# Sheet1.net
KiCad netlist of a schematic drawn in Altium Designer
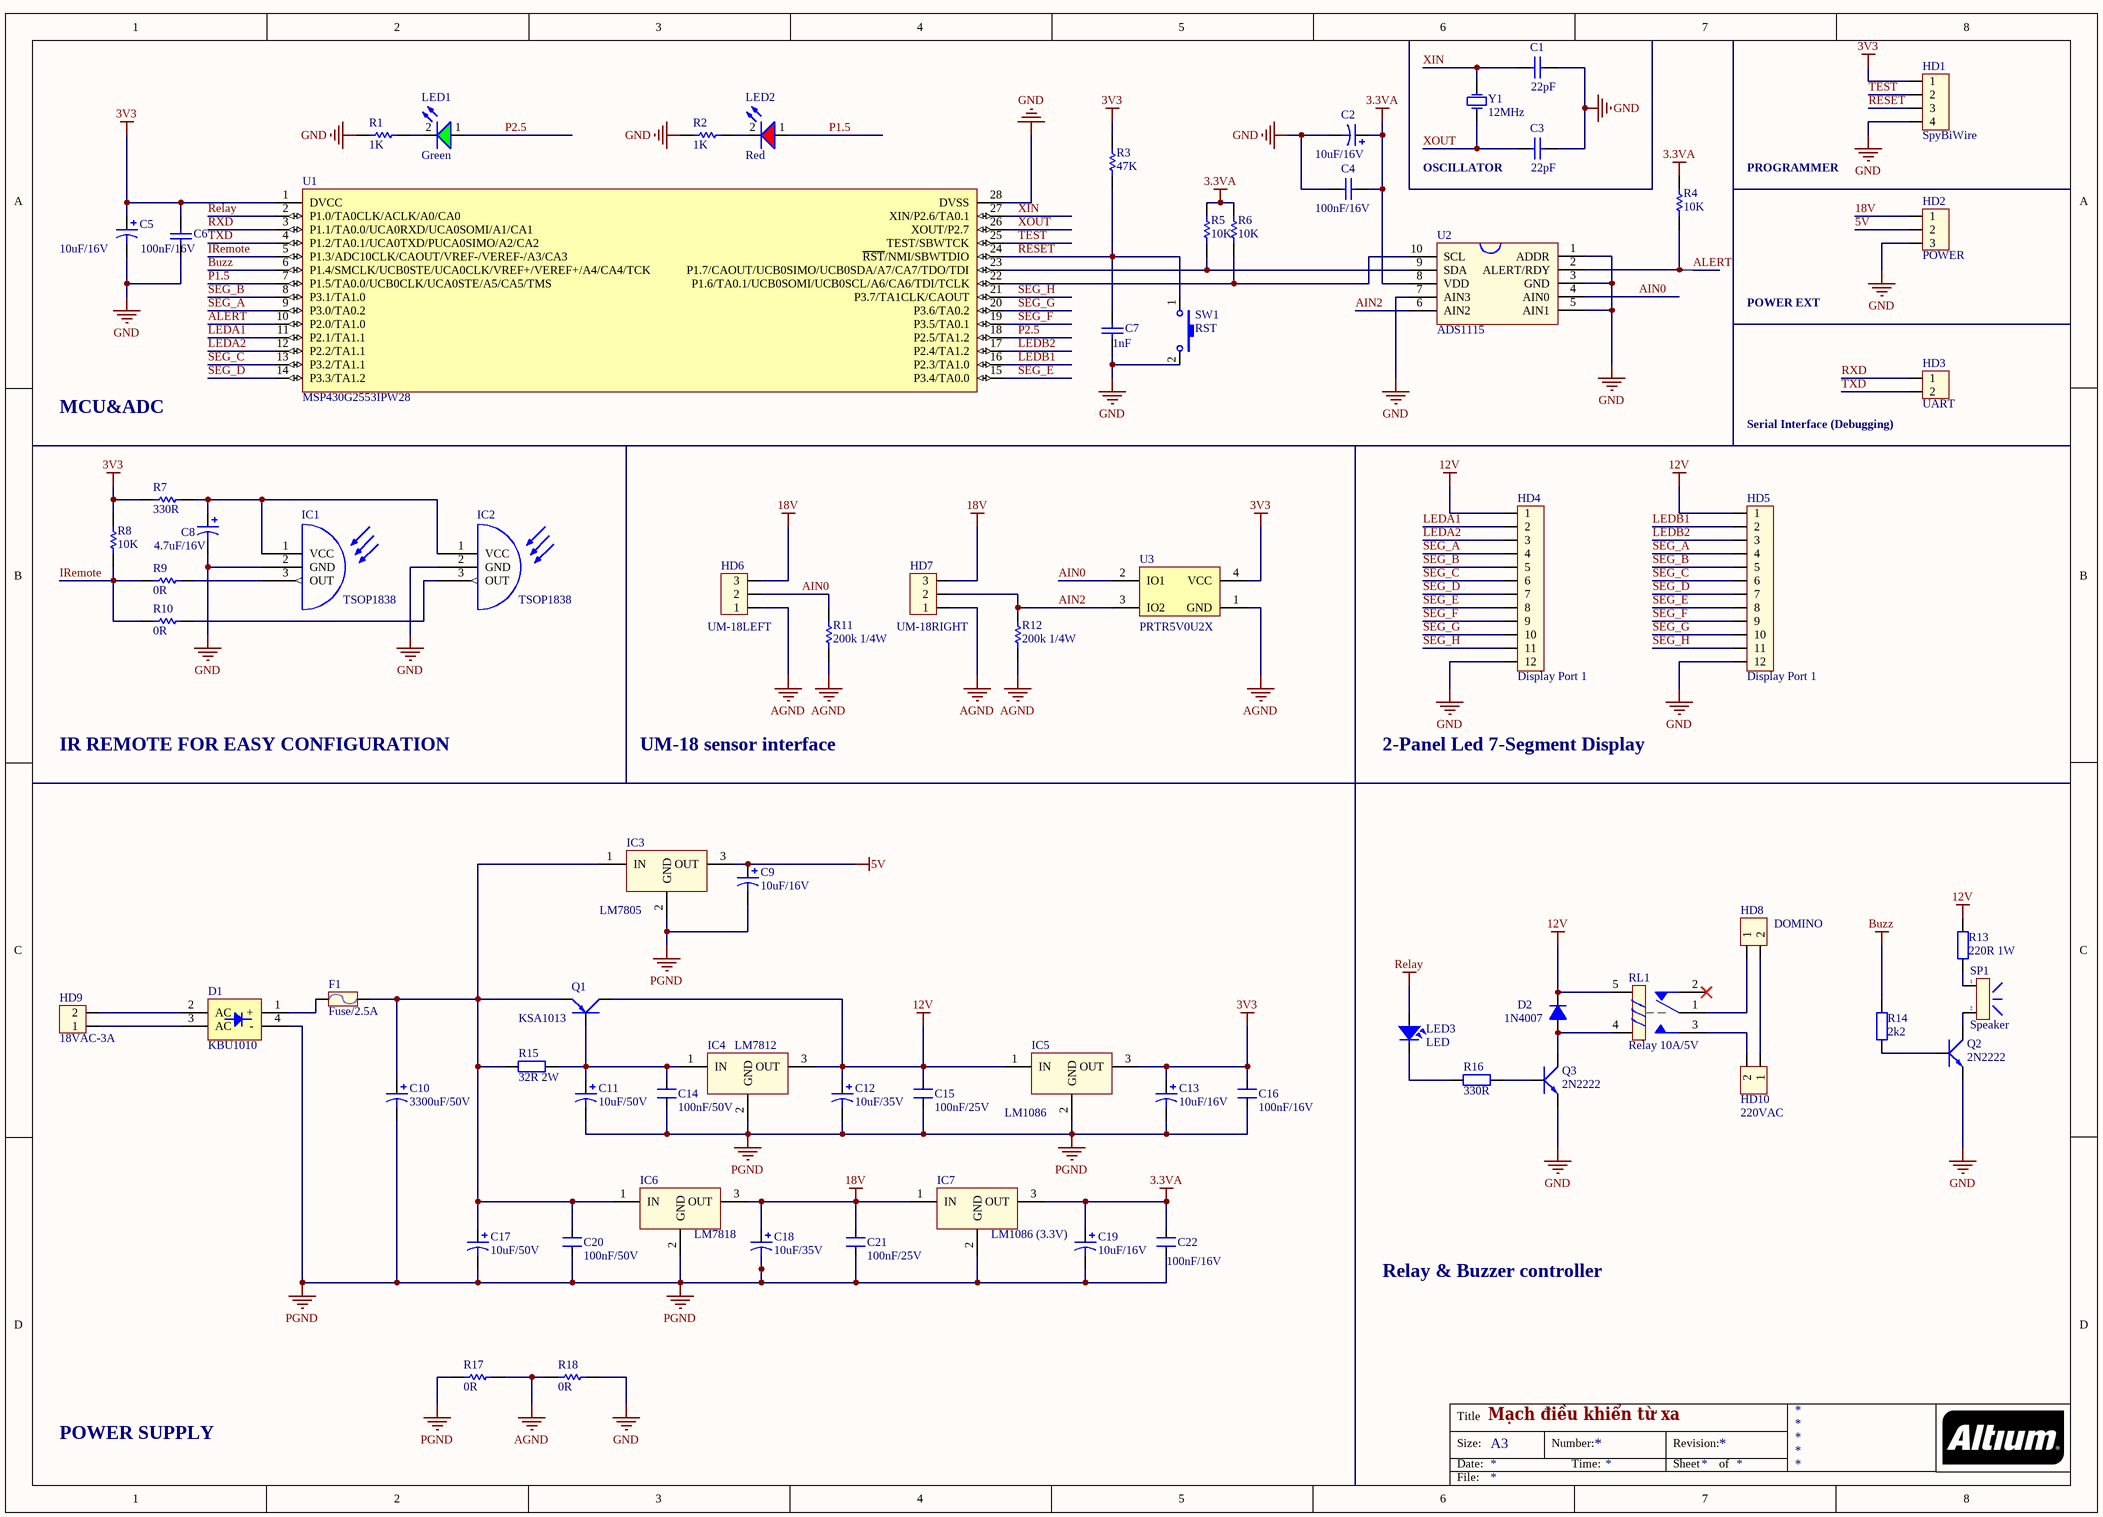
[diagram p0: Sheet1.SchDoc]

(export (version "E")
  (design (tool "Eeschema 10.0.6"))
  (components
    (comp (ref "C1")
      (value "22pF")
      (footprint "Tu gom 104")
      (description "CAP CER 10000PF 50V X7R 0603")
      (fields
        (field (name "MANUFACTURER") "Murata Electronics North America")
        (field (name "MANUFACTURER PART NUMBER") "GRM188R71H103KA01D")
      )
      (libsource (lib "lpson") (part "10nF/50V/C0603/10%"))
    )
    (comp (ref "C2")
      (value "10uF/16V")
      (footprint "CAP_22UF_16V")
      (description "CAP TANT 100UF 6.3V 20% 1411")
      (fields
        (field (name "MANUFACTURER") "Kemet")
        (field (name "MANUFACTURER PART NUMBER") "T491B107M006AT")
      )
      (libsource (lib "lpson") (part "100uF/6.3V/SIZE B/20%"))
    )
    (comp (ref "C3")
      (value "22pF")
      (footprint "Tu gom 104")
      (description "CAP CER 10000PF 50V X7R 0603")
      (fields
        (field (name "MANUFACTURER") "Murata Electronics North America")
        (field (name "MANUFACTURER PART NUMBER") "GRM188R71H103KA01D")
      )
      (libsource (lib "lpson") (part "10nF/50V/C0603/10%"))
    )
    (comp (ref "C4")
      (value "100nF/16V")
      (footprint "C0_1uF")
      (description "CAP CER 10000PF 50V X7R 0603")
      (fields
        (field (name "MANUFACTURER") "Murata Electronics North America")
        (field (name "MANUFACTURER PART NUMBER") "GRM188R71H103KA01D")
      )
      (libsource (lib "lpson") (part "10nF/50V/C0603/10%"))
    )
    (comp (ref "C5")
      (value "10uF/16V")
      (footprint "CP_1")
      (description "CAP TANT 100UF 6.3V 20% 1411")
      (fields
        (field (name "MANUFACTURER") "Kemet")
        (field (name "MANUFACTURER PART NUMBER") "T491B107M006AT")
      )
      (libsource (lib "lpson") (part "100uF/6.3V/SIZE B/20%"))
    )
    (comp (ref "C6")
      (value "100nF/16V")
      (footprint "Tu gom 104")
      (description "CAP CER 10000PF 50V X7R 0603")
      (fields
        (field (name "MANUFACTURER") "Murata Electronics North America")
        (field (name "MANUFACTURER PART NUMBER") "GRM188R71H103KA01D")
      )
      (libsource (lib "lpson") (part "10nF/50V/C0603/10%"))
    )
    (comp (ref "C7")
      (value "1nF")
      (footprint "Tu gom 104")
      (description "CAP CER 10000PF 50V X7R 0603")
      (fields
        (field (name "MANUFACTURER") "Murata Electronics North America")
        (field (name "MANUFACTURER PART NUMBER") "GRM188R71H103KA01D")
      )
      (libsource (lib "lpson") (part "10nF/50V/C0603/10%"))
    )
    (comp (ref "C8")
      (value "4.7uF/16V")
      (footprint "CP_1")
      (description "CAP TANT 100UF 6.3V 20% 1411")
      (fields
        (field (name "MANUFACTURER") "Kemet")
        (field (name "MANUFACTURER PART NUMBER") "T491B107M006AT")
      )
      (libsource (lib "lpson") (part "100uF/6.3V/SIZE B/20%"))
    )
    (comp (ref "C9")
      (value "10uF/16V")
      (footprint "CP_1")
      (description "Polarized Capacitor (Radial)")
      (fields (field (name "Comment") "Cap Pol1") (field (name "PUBLISHER") "Altium Limited"))
      (libsource (lib "lib_thien_schematic") (part "Cap Pol1"))
    )
    (comp (ref "C10")
      (value "3300uF/50V")
      (footprint "CAP_470UF_25V")
      (description "Polarized Capacitor (Radial)")
      (fields (field (name "Comment") "Cap Pol1") (field (name "PUBLISHER") "Altium Limited"))
      (libsource (lib "lib_thien_schematic") (part "Cap Pol1"))
    )
    (comp (ref "C11")
      (value "10uF/50V")
      (footprint "CP_1")
      (description "Polarized Capacitor (Radial)")
      (fields (field (name "Comment") "Cap Pol1") (field (name "PUBLISHER") "Altium Limited"))
      (libsource (lib "lib_thien_schematic") (part "Cap Pol1"))
    )
    (comp (ref "C12")
      (value "10uF/35V")
      (footprint "CP_1")
      (description "Polarized Capacitor (Radial)")
      (fields (field (name "Comment") "Cap Pol1") (field (name "PUBLISHER") "Altium Limited"))
      (libsource (lib "lib_thien_schematic") (part "Cap Pol1"))
    )
    (comp (ref "C13")
      (value "10uF/16V")
      (footprint "CP_1")
      (description "Polarized Capacitor (Radial)")
      (fields (field (name "Comment") "Cap Pol1") (field (name "PUBLISHER") "Altium Limited"))
      (libsource (lib "lib_thien_schematic") (part "Cap Pol1"))
    )
    (comp (ref "C14")
      (value "100nF/50V")
      (footprint "Tu gom 104")
      (description "Cap np 104 => 105pF")
      (libsource (lib "lib_thien_schematic") (part "CN2"))
    )
    (comp (ref "C15")
      (value "100nF/25V")
      (footprint "Tu gom 104")
      (description "Cap np 104 => 105pF")
      (libsource (lib "lib_thien_schematic") (part "CN2"))
    )
    (comp (ref "C16")
      (value "100nF/16V")
      (footprint "Tu gom 104")
      (description "Cap np 104 => 105pF")
      (libsource (lib "lib_thien_schematic") (part "CN2"))
    )
    (comp (ref "C17")
      (value "10uF/50V")
      (footprint "CP_1")
      (description "Polarized Capacitor (Radial)")
      (fields (field (name "Comment") "Cap Pol1") (field (name "PUBLISHER") "Altium Limited"))
      (libsource (lib "lib_thien_schematic") (part "Cap Pol1"))
    )
    (comp (ref "C18")
      (value "10uF/35V")
      (footprint "CP_1")
      (description "Polarized Capacitor (Radial)")
      (fields (field (name "Comment") "Cap Pol1") (field (name "PUBLISHER") "Altium Limited"))
      (libsource (lib "lib_thien_schematic") (part "Cap Pol1"))
    )
    (comp (ref "C19")
      (value "10uF/16V")
      (footprint "CP_1")
      (description "Polarized Capacitor (Radial)")
      (fields (field (name "Comment") "Cap Pol1") (field (name "PUBLISHER") "Altium Limited"))
      (libsource (lib "lib_thien_schematic") (part "Cap Pol1"))
    )
    (comp (ref "C20")
      (value "100nF/50V")
      (footprint "Tu gom 104")
      (description "Cap np 104 => 105pF")
      (libsource (lib "lib_thien_schematic") (part "CN2"))
    )
    (comp (ref "C21")
      (value "100nF/25V")
      (footprint "Tu gom 104")
      (description "Cap np 104 => 105pF")
      (libsource (lib "lib_thien_schematic") (part "CN2"))
    )
    (comp (ref "C22")
      (value "100nF/16V")
      (footprint "Tu gom 104")
      (description "Cap np 104 => 105pF")
      (libsource (lib "VNELEK") (part "CN2"))
    )
    (comp (ref "D1")
      (value "KBU1010")
      (footprint "BRIDGE-10A")
      (description "10A glass passivated bridge rectifier")
      (libsource (lib "lib_thien_schematic") (part "KBU1010"))
    )
    (comp (ref "D2")
      (value "1N4007")
      (footprint "D2A")
      (description "Diode 1A")
      (libsource (lib "VNELEK") (part "D1A"))
    )
    (comp (ref "F1")
      (value "Fuse/2.5A")
      (footprint "FUSE2_5A")
      (description "Fuse")
      (fields (field (name "DESIGNED BY") "VanDungEvn"))
      (libsource (lib "lib_thien_schematic") (part "Fuse"))
    )
    (comp (ref "HD1")
      (value "SpyBiWire")
      (footprint "Header_4")
      (description "Header 4 (Green)")
      (libsource (lib "lpson") (part "Hed4"))
    )
    (comp (ref "HD2")
      (value "POWER")
      (footprint "HD-3")
      (description "Header 3 (Green)")
      (libsource (lib "") (part "Hed3_1"))
    )
    (comp (ref "HD3")
      (value "UART")
      (footprint "HD2")
      (description "Header 2 (Green)")
      (libsource (lib "lpson") (part "Hed2"))
    )
    (comp (ref "HD4")
      (value "Display Port 1")
      (footprint "HD-12")
      (description "Header 12")
      (libsource (lib "lib_thien_schematic") (part "Hed12"))
    )
    (comp (ref "HD5")
      (value "Display Port 1")
      (footprint "HD-12")
      (description "Header 12")
      (libsource (lib "lib_thien_schematic") (part "Hed12"))
    )
    (comp (ref "HD6")
      (value "UM-18LEFT")
      (footprint "Header_3")
      (description "Header 3 (Green)")
      (libsource (lib "lpson") (part "Hed3"))
    )
    (comp (ref "HD7")
      (value "UM-18RIGHT")
      (footprint "Header_3")
      (description "Header 3 (Green)")
      (libsource (lib "lpson") (part "Hed3"))
    )
    (comp (ref "HD8")
      (value "DOMINO")
      (footprint "HDR-2GREEN")
      (description "Header 2 (Green)")
      (libsource (lib "lib_thien_schematic") (part "Hed2"))
    )
    (comp (ref "HD9")
      (value "18VAC-3A")
      (footprint "HDR-2GREEN")
      (description "Header 2 (Green)")
      (libsource (lib "") (part "Hed2_2"))
    )
    (comp (ref "HD10")
      (value "220VAC")
      (footprint "HDR-2GREEN")
      (description "Header 2 (Green)")
      (libsource (lib "") (part "Hed2_1"))
    )
    (comp (ref "IC1")
      (value "TSOP1838")
      (footprint "TSOP-1838")
      (libsource (lib "lib_thien_schematic") (part "TSOP1838"))
    )
    (comp (ref "IC2")
      (value "TSOP1838")
      (footprint "TSOP-1838")
      (libsource (lib "lib_thien_schematic") (part "TSOP1838"))
    )
    (comp (ref "IC3")
      (value "LM7805")
      (footprint "TO-220")
      (description "Linear Regulator")
      (libsource (lib "lib_thien_schematic") (part "LM78xx"))
    )
    (comp (ref "IC4")
      (value "LM7812")
      (footprint "TO-220")
      (description "Linear Regulator")
      (libsource (lib "lib_thien_schematic") (part "LM78xx"))
    )
    (comp (ref "IC5")
      (value "LM1086")
      (footprint "TO-220")
      (description "Linear Regulator")
      (libsource (lib "lib_thien_schematic") (part "LM78xx"))
    )
    (comp (ref "IC6")
      (value "LM7818")
      (footprint "TO-220")
      (description "Linear Regulator")
      (libsource (lib "VNELEK") (part "LM78xx"))
    )
    (comp (ref "IC7")
      (value "LM1086 (3.3V)")
      (footprint "TO-220")
      (description "Linear Regulator")
      (libsource (lib "VNELEK") (part "LM78xx"))
    )
    (comp (ref "LED1")
      (value "Green")
      (footprint "LED_0805_GREEN")
      (description "LED Green 3mm")
      (fields (field (name "Comment") "LED_G_3"))
      (libsource (lib "lpson") (part "LED_GREEN_3MM"))
    )
    (comp (ref "LED2")
      (value "Red")
      (footprint "LED_0805_RED")
      (description "LED Red 5mm")
      (fields (field (name "Comment") "LED_R_5"))
      (libsource (lib "lpson") (part "LED_RED_5MM"))
    )
    (comp (ref "LED3")
      (value "LED")
      (footprint "LED_BLUE_5mm")
      (description "LED Single colour Green and Red")
      (libsource (lib "VNELEK") (part "LED"))
    )
    (comp (ref "Q1")
      (value "KSA1013")
      (footprint "TO92")
      (description "PNP 600mW, ECB")
      (fields (field (name "MANUFACTURER") "Fairchild Semiconductor"))
      (libsource (lib "lib_thien_schematic") (part "A1015"))
    )
    (comp (ref "Q2")
      (value "2N2222")
      (footprint "TO92")
      (description "TRANS GP SS NPN LP 40V TO92")
      (libsource (lib "VNELEK") (part "C1815"))
    )
    (comp (ref "Q3")
      (value "2N2222")
      (footprint "TO92")
      (description "TRANS GP SS NPN LP 40V TO92")
      (libsource (lib "VNELEK") (part "C1815"))
    )
    (comp (ref "R1")
      (value "1K")
      (footprint "R1/2W")
      (description "RES SMD 10K OHM 1% 1/10W 0603")
      (fields
        (field (name "MANUFACTURER") "Yageo")
        (field (name "MANUFACTURER PART NUMBER") "RC0603FR-0710KL")
      )
      (libsource (lib "lpson") (part "10K/R0603/1%"))
    )
    (comp (ref "R2")
      (value "1K")
      (footprint "R1/2W")
      (description "RES SMD 10K OHM 1% 1/10W 0603")
      (fields
        (field (name "MANUFACTURER") "Yageo")
        (field (name "MANUFACTURER PART NUMBER") "RC0603FR-0710KL")
      )
      (libsource (lib "lpson") (part "10K/R0603/1%"))
    )
    (comp (ref "R3")
      (value "47K")
      (footprint "R1/4W")
      (description "RES SMD 10K OHM 1% 1/10W 0603")
      (fields
        (field (name "MANUFACTURER") "Yageo")
        (field (name "MANUFACTURER PART NUMBER") "RC0603FR-0710KL")
      )
      (libsource (lib "lpson") (part "10K/R0603/1%"))
    )
    (comp (ref "R4")
      (value "10K")
      (footprint "R1/2W")
      (description "RES SMD 10K OHM 1% 1/10W 0603")
      (fields
        (field (name "MANUFACTURER") "Yageo")
        (field (name "MANUFACTURER PART NUMBER") "RC0603FR-0710KL")
      )
      (libsource (lib "lpson") (part "10K/R0603/1%"))
    )
    (comp (ref "R5")
      (value "10K")
      (footprint "R1/2W")
      (description "RES SMD 10K OHM 1% 1/10W 0603")
      (fields
        (field (name "MANUFACTURER") "Yageo")
        (field (name "MANUFACTURER PART NUMBER") "RC0603FR-0710KL")
      )
      (libsource (lib "lpson") (part "10K/R0603/1%"))
    )
    (comp (ref "R6")
      (value "10K")
      (footprint "R1/2W")
      (description "RES SMD 10K OHM 1% 1/10W 0603")
      (fields
        (field (name "MANUFACTURER") "Yageo")
        (field (name "MANUFACTURER PART NUMBER") "RC0603FR-0710KL")
      )
      (libsource (lib "lpson") (part "10K/R0603/1%"))
    )
    (comp (ref "R7")
      (value "330R")
      (footprint "R_0805")
      (description "RES SMD 10K OHM 1% 1/10W 0603")
      (fields
        (field (name "MANUFACTURER") "Yageo")
        (field (name "MANUFACTURER PART NUMBER") "RC0603FR-0710KL")
      )
      (libsource (lib "lpson") (part "10K/R0603/1%"))
    )
    (comp (ref "R8")
      (value "10K")
      (footprint "R1/2W")
      (description "RES SMD 10K OHM 1% 1/10W 0603")
      (fields
        (field (name "MANUFACTURER") "Yageo")
        (field (name "MANUFACTURER PART NUMBER") "RC0603FR-0710KL")
      )
      (libsource (lib "lpson") (part "10K/R0603/1%"))
    )
    (comp (ref "R9")
      (value "0R")
      (footprint "R1W")
      (description "RES SMD 10K OHM 1% 1/10W 0603")
      (fields
        (field (name "MANUFACTURER") "Yageo")
        (field (name "MANUFACTURER PART NUMBER") "RC0603FR-0710KL")
      )
      (libsource (lib "lpson") (part "10K/R0603/1%"))
    )
    (comp (ref "R10")
      (value "0R")
      (footprint "R1W")
      (description "RES SMD 10K OHM 1% 1/10W 0603")
      (fields
        (field (name "MANUFACTURER") "Yageo")
        (field (name "MANUFACTURER PART NUMBER") "RC0603FR-0710KL")
      )
      (libsource (lib "lpson") (part "10K/R0603/1%"))
    )
    (comp (ref "R11")
      (value "200k 1/4W")
      (footprint "R1/4W")
      (description "RES SMD 10K OHM 1% 1/10W 0603")
      (fields
        (field (name "MANUFACTURER") "Yageo")
        (field (name "MANUFACTURER PART NUMBER") "RC0603FR-0710KL")
      )
      (libsource (lib "lpson") (part "10K/R0603/1%"))
    )
    (comp (ref "R12")
      (value "200k 1/4W")
      (footprint "R1/4W")
      (description "RES SMD 10K OHM 1% 1/10W 0603")
      (fields
        (field (name "MANUFACTURER") "Yageo")
        (field (name "MANUFACTURER PART NUMBER") "RC0603FR-0710KL")
      )
      (libsource (lib "lpson") (part "10K/R0603/1%"))
    )
    (comp (ref "R13")
      (value "220R 1W")
      (footprint "R_0805")
      (description "Resistor")
      (fields (field (name "Comment") "Res2") (field (name "PUBLISHER") "Altium Limited"))
      (libsource (lib "") (part "Res2_1"))
    )
    (comp (ref "R14")
      (value "2k2")
      (footprint "R1/2W")
      (description "Resistor")
      (fields (field (name "Comment") "Res2") (field (name "PUBLISHER") "Altium Limited"))
      (libsource (lib "") (part "Res2_1"))
    )
    (comp (ref "R15")
      (value "32R 2W")
      (footprint "R_0805")
      (description "Resistor")
      (fields (field (name "Comment") "Res2") (field (name "PUBLISHER") "Altium Limited"))
      (libsource (lib "lib_thien_schematic") (part "Res2"))
    )
    (comp (ref "R16")
      (value "330R")
      (footprint "R_0805")
      (description "Resistor")
      (fields (field (name "Comment") "Res2") (field (name "PUBLISHER") "Altium Limited"))
      (libsource (lib "Miscellaneous Devices") (part "Res2"))
    )
    (comp (ref "R17")
      (value "0R")
      (footprint "R1W")
      (description "RES SMD 10K OHM 1% 1/10W 0603")
      (fields
        (field (name "MANUFACTURER") "Yageo")
        (field (name "MANUFACTURER PART NUMBER") "RC0603FR-0710KL")
      )
      (libsource (lib "lpson") (part "10K/R0603/1%"))
    )
    (comp (ref "R18")
      (value "0R")
      (footprint "R1W")
      (description "RES SMD 10K OHM 1% 1/10W 0603")
      (fields
        (field (name "MANUFACTURER") "Yageo")
        (field (name "MANUFACTURER PART NUMBER") "RC0603FR-0710KL")
      )
      (libsource (lib "lpson") (part "10K/R0603/1%"))
    )
    (comp (ref "RL1")
      (value "Relay 10A/5V")
      (footprint "RL_SPDT_10A")
      (description "Relay SPDT,10A - 12VDC 5 Pin")
      (libsource (lib "VNELEK") (part "Relay 1"))
    )
    (comp (ref "SP1")
      (value "Speaker")
      (footprint "SPEAKER")
      (description "Speaker Chip")
      (libsource (lib "lib_thien_schematic") (part "SPK"))
    )
    (comp (ref "SW1")
      (value "RST")
      (footprint "SW-SMD")
      (description "Switch smd, 2PIN 6x4mm")
      (fields (field (name "Comment") "EVQ-PNF04M") (field (name "PUBLISHER") "Altium Limited"))
      (libsource (lib "lpson") (part "SW EVQ-PNF04M"))
    )
    (comp (ref "U1")
      (value "MSP430G2553IPW28")
      (footprint "TSSOP-28")
      (description "MCU 16bit 16KB 1.8-3.6V 16MHz TSSOP28")
      (libsource (lib "lpson") (part "MSP430G2553IPW28"))
    )
    (comp (ref "U2")
      (value "ADS1115")
      (footprint "TSSOP-10")
      (libsource (lib "lib_thien_schematic") (part "ADS1115"))
    )
    (comp (ref "U3")
      (value "PRTR5V0U2X")
      (footprint "SOT-143")
      (description "ESD protection diode")
      (libsource (lib "lib_thien_schematic") (part "PRTR5V0U2X"))
    )
    (comp (ref "Y1")
      (value "12MHz")
      (footprint "XTAL-12MHz")
      (description "Crystal Oscillator 30ppm 20.000MHz")
      (fields (field (name "Comment") "HC49S-20-C-30-30-F-20.000MHz"))
      (libsource (lib "lpson") (part "HC49S-20-C-30-30-F-20.000MHz"))
    )
  )
  (nets
    (net (code "1") (name "/AIN0") (class "Default")
      (node (ref "HD6") (pin "2") (pinfunction "2_2") (pintype "passive"))
      (node (ref "R11") (pin "2") (pinfunction "2_2") (pintype "passive"))
      (node (ref "U2") (pin "4") (pinfunction "AIN0_4") (pintype "passive"))
      (node (ref "U3") (pin "2") (pinfunction "IO1_2") (pintype "passive"))
    )
    (net (code "2") (name "/AIN2") (class "Default")
      (node (ref "HD7") (pin "2") (pinfunction "2_2") (pintype "passive"))
      (node (ref "R12") (pin "2") (pinfunction "2_2") (pintype "passive"))
      (node (ref "U2") (pin "6") (pinfunction "AIN2_6") (pintype "passive"))
      (node (ref "U3") (pin "3") (pinfunction "IO2_3") (pintype "passive"))
    )
    (net (code "3") (name "/ALERT") (class "Default")
      (node (ref "R4") (pin "1") (pinfunction "1_1") (pintype "passive"))
      (node (ref "U1") (pin "10") (pinfunction "P2.0/TA1.0_10") (pintype "bidirectional"))
      (node (ref "U2") (pin "2") (pinfunction "ALERT/RDY_2") (pintype "passive"))
    )
    (net (code "4") (name "/IRemote") (class "Default")
      (node (ref "R10") (pin "1") (pinfunction "1_1") (pintype "passive"))
      (node (ref "R8") (pin "1") (pinfunction "1_1") (pintype "passive"))
      (node (ref "R9") (pin "1") (pinfunction "1_1") (pintype "passive"))
      (node (ref "U1") (pin "5") (pinfunction "P1.3/ADC10CLK/CAOUT/VREF-/VEREF-/A3/CA3_5") (pintype "bidirectional"))
    )
    (net (code "5") (name "/LEDA1") (class "Default")
      (node (ref "HD4") (pin "2") (pinfunction "2_2") (pintype "passive"))
      (node (ref "U1") (pin "11") (pinfunction "P2.1/TA1.1_11") (pintype "bidirectional"))
    )
    (net (code "6") (name "/LEDA2") (class "Default")
      (node (ref "HD4") (pin "3") (pinfunction "3_3") (pintype "passive"))
      (node (ref "U1") (pin "12") (pinfunction "P2.2/TA1.1_12") (pintype "bidirectional"))
    )
    (net (code "7") (name "/LEDB1") (class "Default")
      (node (ref "HD5") (pin "2") (pinfunction "2_2") (pintype "passive"))
      (node (ref "U1") (pin "16") (pinfunction "P2.3/TA1.0_16") (pintype "bidirectional"))
    )
    (net (code "8") (name "/LEDB2") (class "Default")
      (node (ref "HD5") (pin "3") (pinfunction "3_3") (pintype "passive"))
      (node (ref "U1") (pin "17") (pinfunction "P2.4/TA1.2_17") (pintype "bidirectional"))
    )
    (net (code "9") (name "/P1.5") (class "Default")
      (node (ref "LED2") (pin "1") (pinfunction "A_1") (pintype "passive"))
      (node (ref "U1") (pin "7") (pinfunction "P1.5/TA0.0/UCB0CLK/UCA0STE/A5/CA5/TMS_7") (pintype "bidirectional"))
    )
    (net (code "10") (name "/P2.5") (class "Default")
      (node (ref "LED1") (pin "1") (pinfunction "A_1") (pintype "passive"))
      (node (ref "U1") (pin "18") (pinfunction "P2.5/TA1.2_18") (pintype "bidirectional"))
    )
    (net (code "11") (name "/RESET") (class "Default")
      (node (ref "C7") (pin "2") (pinfunction "2_2") (pintype "passive"))
      (node (ref "HD1") (pin "3") (pinfunction "3_3") (pintype "passive"))
      (node (ref "R3") (pin "1") (pinfunction "1_1") (pintype "passive"))
      (node (ref "SW1") (pin "1") (pinfunction "1_1") (pintype "passive"))
      (node (ref "U1") (pin "24") (pinfunction "~{RST}/NMI/SBWTDIO_24") (pintype "bidirectional"))
    )
    (net (code "12") (name "/RXD") (class "Default")
      (node (ref "HD3") (pin "1") (pinfunction "1_1") (pintype "passive"))
      (node (ref "U1") (pin "3") (pinfunction "P1.1/TA0.0/UCA0RXD/UCA0SOMI/A1/CA1_3") (pintype "bidirectional"))
    )
    (net (code "13") (name "/SEG_A") (class "Default")
      (node (ref "HD4") (pin "4") (pinfunction "4_4") (pintype "passive"))
      (node (ref "HD5") (pin "4") (pinfunction "4_4") (pintype "passive"))
      (node (ref "U1") (pin "9") (pinfunction "P3.0/TA0.2_9") (pintype "bidirectional"))
    )
    (net (code "14") (name "/SEG_B") (class "Default")
      (node (ref "HD4") (pin "5") (pinfunction "5_5") (pintype "passive"))
      (node (ref "HD5") (pin "5") (pinfunction "5_5") (pintype "passive"))
      (node (ref "U1") (pin "8") (pinfunction "P3.1/TA1.0_8") (pintype "bidirectional"))
    )
    (net (code "15") (name "/SEG_C") (class "Default")
      (node (ref "HD4") (pin "6") (pinfunction "6_6") (pintype "passive"))
      (node (ref "HD5") (pin "6") (pinfunction "6_6") (pintype "passive"))
      (node (ref "U1") (pin "13") (pinfunction "P3.2/TA1.1_13") (pintype "bidirectional"))
    )
    (net (code "16") (name "/SEG_D") (class "Default")
      (node (ref "HD4") (pin "7") (pinfunction "7_7") (pintype "passive"))
      (node (ref "HD5") (pin "7") (pinfunction "7_7") (pintype "passive"))
      (node (ref "U1") (pin "14") (pinfunction "P3.3/TA1.2_14") (pintype "bidirectional"))
    )
    (net (code "17") (name "/SEG_E") (class "Default")
      (node (ref "HD4") (pin "8") (pinfunction "8_8") (pintype "passive"))
      (node (ref "HD5") (pin "8") (pinfunction "8_8") (pintype "passive"))
      (node (ref "U1") (pin "15") (pinfunction "P3.4/TA0.0_15") (pintype "bidirectional"))
    )
    (net (code "18") (name "/SEG_F") (class "Default")
      (node (ref "HD4") (pin "9") (pinfunction "9_9") (pintype "passive"))
      (node (ref "HD5") (pin "9") (pinfunction "9_9") (pintype "passive"))
      (node (ref "U1") (pin "19") (pinfunction "P3.5/TA0.1_19") (pintype "bidirectional"))
    )
    (net (code "19") (name "/SEG_G") (class "Default")
      (node (ref "HD4") (pin "10") (pinfunction "10_10") (pintype "passive"))
      (node (ref "HD5") (pin "10") (pinfunction "10_10") (pintype "passive"))
      (node (ref "U1") (pin "20") (pinfunction "P3.6/TA0.2_20") (pintype "bidirectional"))
    )
    (net (code "20") (name "/SEG_H") (class "Default")
      (node (ref "HD4") (pin "11") (pinfunction "11_11") (pintype "passive"))
      (node (ref "HD5") (pin "11") (pinfunction "11_11") (pintype "passive"))
      (node (ref "U1") (pin "21") (pinfunction "P3.7/TA1CLK/CAOUT_21") (pintype "bidirectional"))
    )
    (net (code "21") (name "/TEST") (class "Default")
      (node (ref "HD1") (pin "2") (pinfunction "2_2") (pintype "passive"))
      (node (ref "U1") (pin "25") (pinfunction "TEST/SBWTCK_25") (pintype "bidirectional"))
    )
    (net (code "22") (name "/TXD") (class "Default")
      (node (ref "HD3") (pin "2") (pinfunction "2_2") (pintype "passive"))
      (node (ref "U1") (pin "4") (pinfunction "P1.2/TA0.1/UCA0TXD/PUCA0SIMO/A2/CA2_4") (pintype "bidirectional"))
    )
    (net (code "23") (name "/XIN") (class "Default")
      (node (ref "C1") (pin "1") (pinfunction "1_1") (pintype "passive"))
      (node (ref "U1") (pin "27") (pinfunction "XIN/P2.6/TA0.1_27") (pintype "bidirectional"))
      (node (ref "Y1") (pin "2") (pinfunction "OSC2_2") (pintype "passive"))
    )
    (net (code "24") (name "/XOUT") (class "Default")
      (node (ref "C3") (pin "1") (pinfunction "1_1") (pintype "passive"))
      (node (ref "U1") (pin "26") (pinfunction "XOUT/P2.7_26") (pintype "bidirectional"))
      (node (ref "Y1") (pin "1") (pinfunction "OSC1_1") (pintype "passive"))
    )
    (net (code "25") (name "3.3VA") (class "Default")
      (node (ref "C19") (pin "1") (pinfunction "1_1") (pintype "passive"))
      (node (ref "C2") (pin "1") (pinfunction "1_1") (pintype "passive"))
      (node (ref "C22") (pin "2") (pinfunction "2_2") (pintype "passive"))
      (node (ref "C4") (pin "2") (pinfunction "2_2") (pintype "passive"))
      (node (ref "IC7") (pin "3") (pinfunction "OUT_3") (pintype "passive"))
      (node (ref "R4") (pin "2") (pinfunction "2_2") (pintype "passive"))
      (node (ref "R5") (pin "2") (pinfunction "2_2") (pintype "passive"))
      (node (ref "R6") (pin "2") (pinfunction "2_2") (pintype "passive"))
      (node (ref "U2") (pin "8") (pinfunction "VDD_8") (pintype "passive"))
    )
    (net (code "26") (name "3V3") (class "Default")
      (node (ref "C13") (pin "1") (pinfunction "1_1") (pintype "passive"))
      (node (ref "C16") (pin "2") (pinfunction "2_2") (pintype "passive"))
      (node (ref "C5") (pin "1") (pinfunction "1_1") (pintype "passive"))
      (node (ref "C6") (pin "2") (pinfunction "2_2") (pintype "passive"))
      (node (ref "HD1") (pin "1") (pinfunction "1_1") (pintype "passive"))
      (node (ref "IC5") (pin "3") (pinfunction "OUT_3") (pintype "passive"))
      (node (ref "R3") (pin "2") (pinfunction "2_2") (pintype "passive"))
      (node (ref "R7") (pin "1") (pinfunction "1_1") (pintype "passive"))
      (node (ref "R8") (pin "2") (pinfunction "2_2") (pintype "passive"))
      (node (ref "U1") (pin "1") (pinfunction "DVCC_1") (pintype "power_in"))
      (node (ref "U3") (pin "4") (pinfunction "VCC_4") (pintype "passive"))
    )
    (net (code "27") (name "5V") (class "Default")
      (node (ref "C9") (pin "1") (pinfunction "1_1") (pintype "passive"))
      (node (ref "HD2") (pin "2") (pinfunction "2_2") (pintype "passive"))
      (node (ref "IC3") (pin "3") (pinfunction "OUT_3") (pintype "passive"))
    )
    (net (code "28") (name "12V") (class "Default")
      (node (ref "C12") (pin "1") (pinfunction "1_1") (pintype "passive"))
      (node (ref "C15") (pin "2") (pinfunction "2_2") (pintype "passive"))
      (node (ref "D2") (pin "2") (pinfunction "K_2") (pintype "passive"))
      (node (ref "HD4") (pin "1") (pinfunction "1_1") (pintype "passive"))
      (node (ref "HD5") (pin "1") (pinfunction "1_1") (pintype "passive"))
      (node (ref "IC4") (pin "3") (pinfunction "OUT_3") (pintype "passive"))
      (node (ref "IC5") (pin "1") (pinfunction "IN_1") (pintype "passive"))
      (node (ref "Q1") (pin "2") (pinfunction "C_2") (pintype "passive"))
      (node (ref "R13") (pin "2") (pinfunction "2_2") (pintype "passive"))
      (node (ref "RL1") (pin "5") (pinfunction "5_5") (pintype "passive"))
    )
    (net (code "29") (name "18V") (class "Default")
      (node (ref "C18") (pin "1") (pinfunction "1_1") (pintype "passive"))
      (node (ref "C21") (pin "2") (pinfunction "2_2") (pintype "passive"))
      (node (ref "HD2") (pin "1") (pinfunction "1_1") (pintype "passive"))
      (node (ref "HD6") (pin "3") (pinfunction "3_3") (pintype "passive"))
      (node (ref "HD7") (pin "3") (pinfunction "3_3") (pintype "passive"))
      (node (ref "IC6") (pin "3") (pinfunction "OUT_3") (pintype "passive"))
      (node (ref "IC7") (pin "1") (pinfunction "IN_1") (pintype "passive"))
    )
    (net (code "30") (name "AGND") (class "Default")
      (node (ref "HD6") (pin "1") (pinfunction "1_1") (pintype "passive"))
      (node (ref "HD7") (pin "1") (pinfunction "1_1") (pintype "passive"))
      (node (ref "R11") (pin "1") (pinfunction "1_1") (pintype "passive"))
      (node (ref "R12") (pin "1") (pinfunction "1_1") (pintype "passive"))
      (node (ref "R17") (pin "2") (pinfunction "2_2") (pintype "passive"))
      (node (ref "R18") (pin "1") (pinfunction "1_1") (pintype "passive"))
      (node (ref "U3") (pin "1") (pinfunction "GND_1") (pintype "passive"))
    )
    (net (code "31") (name "Buzz") (class "Default")
      (node (ref "R14") (pin "1") (pinfunction "1_1") (pintype "passive"))
      (node (ref "U1") (pin "6") (pinfunction "P1.4/SMCLK/UCB0STE/UCA0CLK/VREF+/VEREF+/A4/CA4/TCK_6") (pintype "bidirectional"))
    )
    (net (code "32") (name "GND") (class "Default")
      (node (ref "C1") (pin "2") (pinfunction "2_2") (pintype "passive"))
      (node (ref "C2") (pin "2") (pinfunction "2_2") (pintype "passive"))
      (node (ref "C3") (pin "2") (pinfunction "2_2") (pintype "passive"))
      (node (ref "C4") (pin "1") (pinfunction "1_1") (pintype "passive"))
      (node (ref "C5") (pin "2") (pinfunction "2_2") (pintype "passive"))
      (node (ref "C6") (pin "1") (pinfunction "1_1") (pintype "passive"))
      (node (ref "C7") (pin "1") (pinfunction "1_1") (pintype "passive"))
      (node (ref "C8") (pin "2") (pinfunction "2_2") (pintype "passive"))
      (node (ref "HD1") (pin "4") (pinfunction "4_4") (pintype "passive"))
      (node (ref "HD2") (pin "3") (pinfunction "3_3") (pintype "passive"))
      (node (ref "HD4") (pin "12") (pinfunction "12_12") (pintype "passive"))
      (node (ref "HD5") (pin "12") (pinfunction "12_12") (pintype "passive"))
      (node (ref "IC1") (pin "2") (pinfunction "GND_2") (pintype "power_in"))
      (node (ref "IC2") (pin "2") (pinfunction "GND_2") (pintype "power_in"))
      (node (ref "Q2") (pin "1") (pinfunction "E_1") (pintype "passive"))
      (node (ref "Q3") (pin "1") (pinfunction "E_1") (pintype "passive"))
      (node (ref "R1") (pin "2") (pinfunction "2_2") (pintype "passive"))
      (node (ref "R18") (pin "2") (pinfunction "2_2") (pintype "passive"))
      (node (ref "R2") (pin "2") (pinfunction "2_2") (pintype "passive"))
      (node (ref "SW1") (pin "2") (pinfunction "2_2") (pintype "passive"))
      (node (ref "U1") (pin "28") (pinfunction "DVSS_28") (pintype "power_in"))
      (node (ref "U2") (pin "1") (pinfunction "ADDR_1") (pintype "passive"))
      (node (ref "U2") (pin "3") (pinfunction "GND_3") (pintype "passive"))
      (node (ref "U2") (pin "5") (pinfunction "AIN1_5") (pintype "passive"))
      (node (ref "U2") (pin "7") (pinfunction "AIN3_7") (pintype "passive"))
    )
    (net (code "33") (name "Net-(D1-+)") (class "Default")
      (node (ref "D1") (pin "1") (pinfunction "+_1") (pintype "power_in"))
      (node (ref "F1") (pin "1") (pinfunction "1_1") (pintype "passive"))
    )
    (net (code "34") (name "Net-(D1-AC-Pad2)") (class "Default")
      (node (ref "D1") (pin "2") (pinfunction "AC_2") (pintype "power_in"))
      (node (ref "HD9") (pin "2") (pinfunction "2_2") (pintype "passive"))
    )
    (net (code "35") (name "Net-(D1-AC-Pad3)") (class "Default")
      (node (ref "D1") (pin "3") (pinfunction "AC_3") (pintype "power_in"))
      (node (ref "HD9") (pin "1") (pinfunction "1_1") (pintype "passive"))
    )
    (net (code "36") (name "Net-(D2-A)") (class "Default")
      (node (ref "D2") (pin "1") (pinfunction "A_1") (pintype "passive"))
      (node (ref "Q3") (pin "3") (pinfunction "C_3") (pintype "passive"))
      (node (ref "RL1") (pin "4") (pinfunction "4_4") (pintype "passive"))
    )
    (net (code "37") (name "Net-(HD8-Pad1)") (class "Default")
      (node (ref "HD8") (pin "1") (pinfunction "1_1") (pintype "passive"))
      (node (ref "RL1") (pin "1") (pinfunction "1_1") (pintype "passive"))
    )
    (net (code "38") (name "Net-(HD10-Pad1)") (class "Default")
      (node (ref "HD10") (pin "1") (pinfunction "1_1") (pintype "passive"))
      (node (ref "HD8") (pin "2") (pinfunction "2_2") (pintype "passive"))
    )
    (net (code "39") (name "Net-(HD10-Pad2)") (class "Default")
      (node (ref "HD10") (pin "2") (pinfunction "2_2") (pintype "passive"))
      (node (ref "RL1") (pin "3") (pinfunction "3_3") (pintype "passive"))
    )
    (net (code "40") (name "Net-(IC1-OUT)") (class "Default")
      (node (ref "IC1") (pin "3") (pinfunction "OUT_3") (pintype "output"))
      (node (ref "R9") (pin "2") (pinfunction "2_2") (pintype "passive"))
    )
    (net (code "41") (name "Net-(IC1-VCC)") (class "Default")
      (node (ref "C8") (pin "1") (pinfunction "1_1") (pintype "passive"))
      (node (ref "IC1") (pin "1") (pinfunction "VCC_1") (pintype "power_in"))
      (node (ref "IC2") (pin "1") (pinfunction "VCC_1") (pintype "power_in"))
      (node (ref "R7") (pin "2") (pinfunction "2_2") (pintype "passive"))
    )
    (net (code "42") (name "Net-(IC2-OUT)") (class "Default")
      (node (ref "IC2") (pin "3") (pinfunction "OUT_3") (pintype "output"))
      (node (ref "R10") (pin "2") (pinfunction "2_2") (pintype "passive"))
    )
    (net (code "43") (name "Net-(IC3-IN)") (class "Default")
      (node (ref "C10") (pin "1") (pinfunction "1_1") (pintype "passive"))
      (node (ref "C17") (pin "1") (pinfunction "1_1") (pintype "passive"))
      (node (ref "C20") (pin "2") (pinfunction "2_2") (pintype "passive"))
      (node (ref "F1") (pin "2") (pinfunction "2_2") (pintype "passive"))
      (node (ref "IC3") (pin "1") (pinfunction "IN_1") (pintype "passive"))
      (node (ref "IC6") (pin "1") (pinfunction "IN_1") (pintype "passive"))
      (node (ref "Q1") (pin "1") (pinfunction "E_1") (pintype "passive"))
      (node (ref "R15") (pin "1") (pinfunction "1_1") (pintype "passive"))
    )
    (net (code "44") (name "Net-(IC4-IN)") (class "Default")
      (node (ref "C11") (pin "1") (pinfunction "1_1") (pintype "passive"))
      (node (ref "C14") (pin "2") (pinfunction "2_2") (pintype "passive"))
      (node (ref "IC4") (pin "1") (pinfunction "IN_1") (pintype "passive"))
      (node (ref "Q1") (pin "3") (pinfunction "B_3") (pintype "passive"))
      (node (ref "R15") (pin "2") (pinfunction "2_2") (pintype "passive"))
    )
    (net (code "45") (name "Net-(LED1-K)") (class "Default")
      (node (ref "LED1") (pin "2") (pinfunction "K_2") (pintype "passive"))
      (node (ref "R1") (pin "1") (pinfunction "1_1") (pintype "passive"))
    )
    (net (code "46") (name "Net-(LED2-K)") (class "Default")
      (node (ref "LED2") (pin "2") (pinfunction "K_2") (pintype "passive"))
      (node (ref "R2") (pin "1") (pinfunction "1_1") (pintype "passive"))
    )
    (net (code "47") (name "Net-(LED3-Pad2)") (class "Default")
      (node (ref "LED3") (pin "2") (pinfunction "2_2") (pintype "passive"))
      (node (ref "R16") (pin "2") (pinfunction "2_2") (pintype "passive"))
    )
    (net (code "48") (name "Net-(Q2-B)") (class "Default")
      (node (ref "Q2") (pin "2") (pinfunction "B_2") (pintype "passive"))
      (node (ref "R14") (pin "2") (pinfunction "2_2") (pintype "passive"))
    )
    (net (code "49") (name "Net-(Q2-C)") (class "Default")
      (node (ref "Q2") (pin "3") (pinfunction "C_3") (pintype "passive"))
      (node (ref "SP1") (pin "2") (pinfunction "2_2") (pintype "passive"))
    )
    (net (code "50") (name "Net-(Q3-B)") (class "Default")
      (node (ref "Q3") (pin "2") (pinfunction "B_2") (pintype "passive"))
      (node (ref "R16") (pin "1") (pinfunction "1_1") (pintype "passive"))
    )
    (net (code "51") (name "Net-(R13-Pad1)") (class "Default")
      (node (ref "R13") (pin "1") (pinfunction "1_1") (pintype "passive"))
      (node (ref "SP1") (pin "1") (pinfunction "1_1") (pintype "passive"))
    )
    (net (code "52") (name "Net-(U1-P1.6{slash}TA0.1{slash}UCB0SOMI{slash}UCB0SCL{slash}A6{slash}CA6{slash}TDI{slash}TCLK)") (class "Default")
      (node (ref "R6") (pin "1") (pinfunction "1_1") (pintype "passive"))
      (node (ref "U1") (pin "22") (pinfunction "P1.6/TA0.1/UCB0SOMI/UCB0SCL/A6/CA6/TDI/TCLK_22") (pintype "bidirectional"))
      (node (ref "U2") (pin "10") (pinfunction "SCL_10") (pintype "passive"))
    )
    (net (code "53") (name "Net-(U1-P1.7{slash}CAOUT{slash}UCB0SIMO{slash}UCB0SDA{slash}A7{slash}CA7{slash}TDO{slash}TDI)") (class "Default")
      (node (ref "R5") (pin "1") (pinfunction "1_1") (pintype "passive"))
      (node (ref "U1") (pin "23") (pinfunction "P1.7/CAOUT/UCB0SIMO/UCB0SDA/A7/CA7/TDO/TDI_23") (pintype "bidirectional"))
      (node (ref "U2") (pin "9") (pinfunction "SDA_9") (pintype "passive"))
    )
    (net (code "54") (name "PGND") (class "Default")
      (node (ref "C10") (pin "2") (pinfunction "2_2") (pintype "passive"))
      (node (ref "C11") (pin "2") (pinfunction "2_2") (pintype "passive"))
      (node (ref "C12") (pin "2") (pinfunction "2_2") (pintype "passive"))
      (node (ref "C13") (pin "2") (pinfunction "2_2") (pintype "passive"))
      (node (ref "C14") (pin "1") (pinfunction "1_1") (pintype "passive"))
      (node (ref "C15") (pin "1") (pinfunction "1_1") (pintype "passive"))
      (node (ref "C16") (pin "1") (pinfunction "1_1") (pintype "passive"))
      (node (ref "C17") (pin "2") (pinfunction "2_2") (pintype "passive"))
      (node (ref "C18") (pin "2") (pinfunction "2_2") (pintype "passive"))
      (node (ref "C19") (pin "2") (pinfunction "2_2") (pintype "passive"))
      (node (ref "C20") (pin "1") (pinfunction "1_1") (pintype "passive"))
      (node (ref "C21") (pin "1") (pinfunction "1_1") (pintype "passive"))
      (node (ref "C22") (pin "1") (pinfunction "1_1") (pintype "passive"))
      (node (ref "C9") (pin "2") (pinfunction "2_2") (pintype "passive"))
      (node (ref "D1") (pin "4") (pinfunction "-_4") (pintype "power_in"))
      (node (ref "IC3") (pin "2") (pinfunction "GND_2") (pintype "passive"))
      (node (ref "IC4") (pin "2") (pinfunction "GND_2") (pintype "passive"))
      (node (ref "IC5") (pin "2") (pinfunction "GND_2") (pintype "passive"))
      (node (ref "IC6") (pin "2") (pinfunction "GND_2") (pintype "passive"))
      (node (ref "IC7") (pin "2") (pinfunction "GND_2") (pintype "passive"))
      (node (ref "R17") (pin "1") (pinfunction "1_1") (pintype "passive"))
    )
    (net (code "55") (name "Relay") (class "Default")
      (node (ref "LED3") (pin "1") (pinfunction "1_1") (pintype "passive"))
      (node (ref "U1") (pin "2") (pinfunction "P1.0/TA0CLK/ACLK/A0/CA0_2") (pintype "bidirectional"))
    )
    (net (code "56") (name "unconnected-(RL1-Pad2)") (class "Default")
      (node (ref "RL1") (pin "2") (pinfunction "2_2") (pintype "passive+no_connect"))
    )
  )
)
